# PWM.net
KiCad netlist of a schematic drawn in Altium Designer
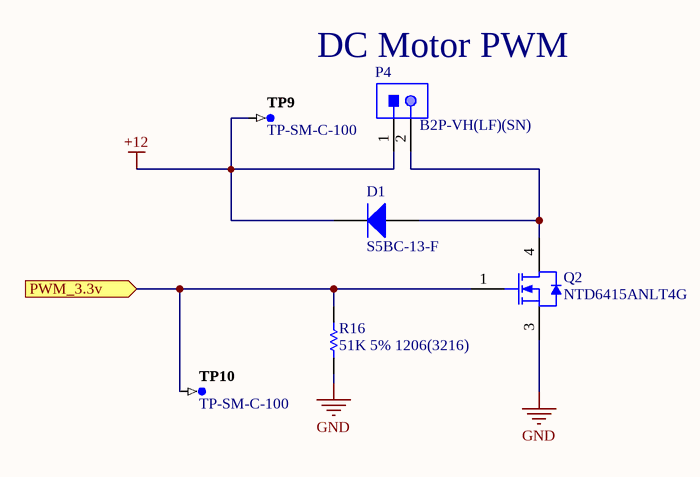
[diagram p0: PWM.SchDoc]

(export (version "E")
  (design (tool "Eeschema 10.0.6"))
  (components
    (comp (ref "D1")
      (value "S5BC-13-F")
      (footprint "DIOD-S5xC_V")
      (fields (field (name "MANUFACTURER") "Diodes Inc"))
      (libsource (lib "Altium Content Vault") (part "D-AK-2"))
    )
    (comp (ref "P4")
      (value "B2P-VH(LF)(SN)")
      (footprint "JST-B2P-VH(LF)(SN)_V")
      (fields (field (name "TOLERANCE") "5%"))
      (libsource (lib "Altium Content Vault") (part "CN-1P-M-R2"))
    )
    (comp (ref "Q2")
      (value "NTD6415ANLT4G")
      (footprint "ONSC-DPAK-3-369AA-01_V")
      (description "N-Channel Power MOSFET, 100 V, 23 A, 56 mOhm, 3-Pin DPAK, Pb-Free, Tape and Reel")
      (fields (field (name "MANUFACTURER") "On Semiconductor"))
      (libsource (lib "Altium Content Vault") (part "ONSC-NMOS-G1S3D4-3_B"))
    )
    (comp (ref "R16")
      (value "51K 5% 1206(3216)")
      (footprint "RESC1206(3216)_M")
      (description "51K 0.25W 5% 1206 (3216 Metric)  SMD")
      (fields (field (name "POWER") "0.25 W") (field (name "TOLERANCE") "5 %"))
      (libsource (lib "Altium Content Vault") (part "RES"))
    )
    (comp (ref "TP9")
      (value "TP-SM-C-100")
      (footprint "TP-SM-C-100")
      (description "Test Point, Surface Mount, Circular, Pad Diameter 1 mm")
      (fields (field (name "MANUFACTURER") "No Vendor"))
      (libsource (lib "Altium Content Vault") (part "TP-SM"))
    )
    (comp (ref "TP10")
      (value "TP-SM-C-100")
      (footprint "TP-SM-C-100")
      (description "Test Point, Surface Mount, Circular, Pad Diameter 1 mm")
      (fields (field (name "MANUFACTURER") "No Vendor"))
      (libsource (lib "Altium Content Vault") (part "TP-SM"))
    )
  )
  (nets
    (net (code "1") (name "+12") (class "Default")
      (node (ref "D1") (pin "2") (pinfunction "K_2") (pintype "passive"))
      (node (ref "P4") (pin "1") (pinfunction "1_1") (pintype "passive"))
      (node (ref "TP9") (pin "1") (pinfunction "1_1") (pintype "input"))
    )
    (net (code "2") (name "/PWM_3.3v") (class "Default")
      (node (ref "Q2") (pin "1") (pinfunction "G_1") (pintype "passive"))
      (node (ref "R16") (pin "2") (pinfunction "2_2") (pintype "passive"))
      (node (ref "TP10") (pin "1") (pinfunction "1_1") (pintype "input"))
    )
    (net (code "3") (name "GND") (class "Default")
      (node (ref "Q2") (pin "3") (pinfunction "S_3") (pintype "passive"))
      (node (ref "R16") (pin "1") (pinfunction "1_1") (pintype "passive"))
    )
    (net (code "4") (name "Net-(D1-A)") (class "Default")
      (node (ref "D1") (pin "1") (pinfunction "A_1") (pintype "passive"))
      (node (ref "P4") (pin "2") (pinfunction "2_2") (pintype "passive"))
      (node (ref "Q2") (pin "4") (pinfunction "D_4") (pintype "passive"))
    )
  )
)
